# POWER.net
KiCad netlist of a schematic drawn in Altium Designer
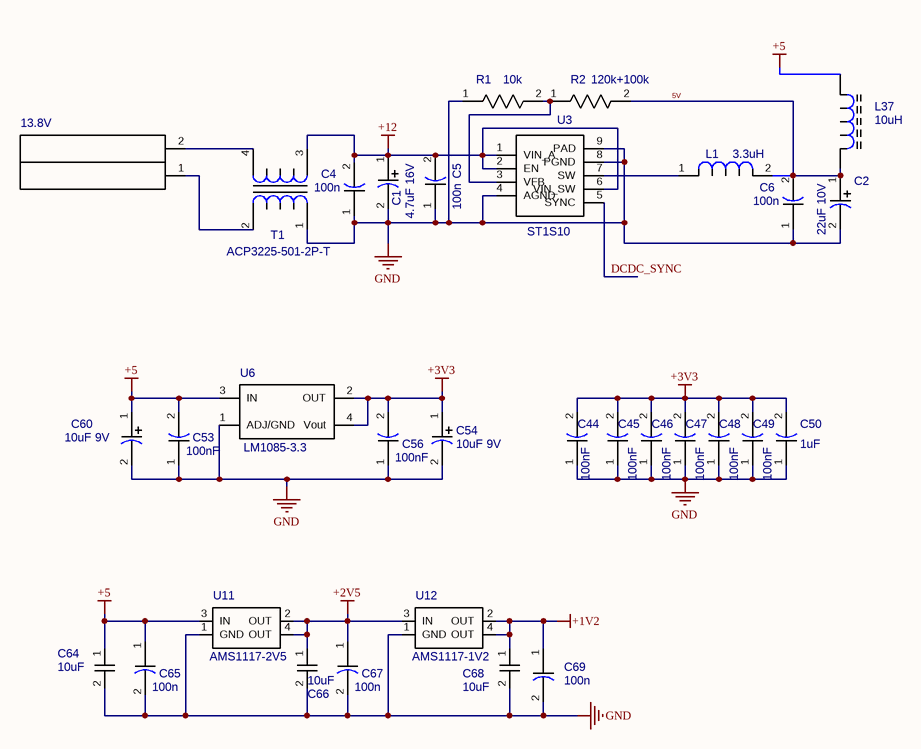
[diagram p0: POWER.SchDoc]

(export (version "E")
  (design (tool "Eeschema 10.0.6"))
  (components
    (comp (ref "13.8V") (value "JX2") (footprint "JX2") (libsource (lib "*") (part "JX2")))
    (comp (ref "C1")
      (value "4.7uF 16V")
      (footprint "CAPAE_6.6x6.6h5.4")
      (description "CAPAE_6.6x6.6h5.4")
      (libsource (lib "*") (part "CAPAE_6.6x6.6h5.4"))
    )
    (comp (ref "C2")
      (value "22uF 10V")
      (footprint "CAPAE_4.3x4.3h5.4")
      (description "CAPAE_4.3x4.3h5.4")
      (libsource (lib "*") (part "CAPAE_4.3x4.3h5.4"))
    )
    (comp (ref "C4")
      (value "100n")
      (footprint "CAP_0805")
      (description "CAP_0805")
      (libsource (lib "*") (part "CAP_0805"))
    )
    (comp (ref "C5")
      (value "100n")
      (footprint "CAP_0805")
      (description "CAP_0805")
      (libsource (lib "*") (part "CAP_0805"))
    )
    (comp (ref "C6")
      (value "100n")
      (footprint "CAP_0805")
      (description "CAP_0805")
      (libsource (lib "*") (part "CAP_0805"))
    )
    (comp (ref "C44")
      (value "100nF")
      (footprint "CAP_0805")
      (description "CAP_0805")
      (libsource (lib "*") (part "CAP_0805"))
    )
    (comp (ref "C45")
      (value "100nF")
      (footprint "CAP_0805")
      (description "CAP_0805")
      (libsource (lib "*") (part "CAP_0805"))
    )
    (comp (ref "C46")
      (value "100nF")
      (footprint "CAP_0805")
      (description "CAP_0805")
      (libsource (lib "*") (part "CAP_0805"))
    )
    (comp (ref "C47")
      (value "100nF")
      (footprint "CAP_0805")
      (description "CAP_0805")
      (libsource (lib "*") (part "CAP_0805"))
    )
    (comp (ref "C48")
      (value "100nF")
      (footprint "CAP_0805")
      (description "CAP_0805")
      (libsource (lib "*") (part "CAP_0805"))
    )
    (comp (ref "C49")
      (value "100nF")
      (footprint "CAP_0805")
      (description "CAP_0805")
      (libsource (lib "*") (part "CAP_0805"))
    )
    (comp (ref "C50")
      (value "1uF")
      (footprint "CAP_0805")
      (description "CAP_0805")
      (fields (field (name "Comment") "10uF"))
      (libsource (lib "*") (part "CAP_0805"))
    )
    (comp (ref "C53")
      (value "100nF")
      (footprint "CAP_0805")
      (description "CAP_0805")
      (libsource (lib "*") (part "CAP_0805"))
    )
    (comp (ref "C54")
      (value "10uF 9V")
      (footprint "CAPAE_4.3x4.3h5.4")
      (description "CAPAE_4.3x4.3h5.4")
      (libsource (lib "*") (part "CAPAE_4.3x4.3h5.4"))
    )
    (comp (ref "C56")
      (value "100nF")
      (footprint "CAP_0805")
      (description "CAP_0805")
      (libsource (lib "*") (part "CAP_0805"))
    )
    (comp (ref "C60")
      (value "10uF 9V")
      (footprint "CAPAE_4.3x4.3h5.4")
      (description "CAPAE_4.3x4.3h5.4")
      (libsource (lib "*") (part "CAPAE_4.3x4.3h5.4"))
    )
    (comp (ref "C64")
      (value "10uF")
      (footprint "C0805")
      (description "C0805")
      (libsource (lib "*") (part "C0805"))
    )
    (comp (ref "C65")
      (value "100n")
      (footprint "CAP_0805")
      (description "CAP_0805")
      (libsource (lib "*") (part "CAP_0805"))
    )
    (comp (ref "C66")
      (value "10uF")
      (footprint "C0805")
      (description "C0805")
      (libsource (lib "*") (part "C0805"))
    )
    (comp (ref "C67")
      (value "100n")
      (footprint "CAP_0805")
      (description "CAP_0805")
      (libsource (lib "*") (part "CAP_0805"))
    )
    (comp (ref "C68")
      (value "10uF")
      (footprint "C0805")
      (description "C0805")
      (libsource (lib "*") (part "C0805"))
    )
    (comp (ref "C69")
      (value "100n")
      (footprint "CAP_0805")
      (description "CAP_0805")
      (libsource (lib "*") (part "CAP_0805"))
    )
    (comp (ref "L1")
      (value "3.3uH")
      (footprint "IND_1812")
      (description "IND_1812")
      (libsource (lib "*") (part "IND_1812"))
    )
    (comp (ref "L37")
      (value "10uH")
      (footprint "IND_FERRITE_CORE")
      (description "Inductor")
      (libsource (lib "MOTHERBOARD_1") (part "IND_FERRITE_CORE"))
    )
    (comp (ref "R1")
      (value "10k")
      (footprint "RES_0805")
      (description "RES_0805")
      (libsource (lib "*") (part "RES_0805"))
    )
    (comp (ref "R2")
      (value "120k+100k")
      (footprint "RES_0805")
      (description "RES_0805")
      (libsource (lib "*") (part "RES_0805"))
    )
    (comp (ref "T1")
      (value "ACP3225-501-2P-T")
      (footprint "TRANSF_ICORE")
      (description "Transformer")
      (libsource (lib "*") (part "TRANSF_ICORE"))
    )
    (comp (ref "U3") (value "ST1S10") (footprint "ST1S10") (libsource (lib "*") (part "ST1S10")))
    (comp (ref "U6") (value "LM1085-3.3") (footprint "LM1085-3.3") (libsource (lib "*") (part "LM1085-3.3")))
    (comp (ref "U11") (value "AMS1117-2V5") (footprint "AMS1117") (libsource (lib "*") (part "AMS1117")))
    (comp (ref "U12") (value "AMS1117-1V2") (footprint "AMS1117") (libsource (lib "*") (part "AMS1117")))
  )
  (nets
    (net (code "1") (name "+1V2") (class "Default")
      (node (ref "C68") (pin "1") (pinfunction "1_1") (pintype "passive"))
      (node (ref "C69") (pin "1") (pinfunction "1_1") (pintype "passive"))
      (node (ref "U12") (pin "2") (pinfunction "OUT_2") (pintype "passive"))
      (node (ref "U12") (pin "4") (pinfunction "OUT_4") (pintype "passive"))
    )
    (net (code "2") (name "+2V5") (class "Default")
      (node (ref "C66") (pin "1") (pinfunction "1_1") (pintype "passive"))
      (node (ref "C67") (pin "1") (pinfunction "1_1") (pintype "passive"))
      (node (ref "U11") (pin "2") (pinfunction "OUT_2") (pintype "passive"))
      (node (ref "U11") (pin "4") (pinfunction "OUT_4") (pintype "passive"))
      (node (ref "U12") (pin "3") (pinfunction "IN_3") (pintype "passive"))
    )
    (net (code "3") (name "+3V3") (class "Default")
      (node (ref "C44") (pin "2") (pinfunction "2_2") (pintype "passive"))
      (node (ref "C45") (pin "2") (pinfunction "2_2") (pintype "passive"))
      (node (ref "C46") (pin "2") (pinfunction "2_2") (pintype "passive"))
      (node (ref "C47") (pin "2") (pinfunction "2_2") (pintype "passive"))
      (node (ref "C48") (pin "2") (pinfunction "2_2") (pintype "passive"))
      (node (ref "C49") (pin "2") (pinfunction "2_2") (pintype "passive"))
      (node (ref "C50") (pin "2") (pinfunction "2_2") (pintype "passive"))
      (node (ref "C54") (pin "1") (pinfunction "PLUS_1") (pintype "passive"))
      (node (ref "C56") (pin "2") (pinfunction "2_2") (pintype "passive"))
      (node (ref "U6") (pin "2") (pinfunction "OUT_2") (pintype "passive"))
      (node (ref "U6") (pin "4") (pinfunction "Vout_4") (pintype "passive"))
    )
    (net (code "4") (name "+5") (class "Default")
      (node (ref "C53") (pin "2") (pinfunction "2_2") (pintype "passive"))
      (node (ref "C60") (pin "1") (pinfunction "PLUS_1") (pintype "passive"))
      (node (ref "C64") (pin "1") (pinfunction "1_1") (pintype "passive"))
      (node (ref "C65") (pin "1") (pinfunction "1_1") (pintype "passive"))
      (node (ref "L37") (pin "1") (pinfunction "A_1") (pintype "passive"))
      (node (ref "U11") (pin "3") (pinfunction "IN_3") (pintype "passive"))
      (node (ref "U6") (pin "3") (pinfunction "IN_3") (pintype "passive"))
    )
    (net (code "5") (name "+12") (class "Default")
      (node (ref "C1") (pin "1") (pinfunction "PLUS_1") (pintype "passive"))
      (node (ref "C4") (pin "2") (pinfunction "2_2") (pintype "passive"))
      (node (ref "C5") (pin "2") (pinfunction "2_2") (pintype "passive"))
      (node (ref "T1") (pin "3") (pinfunction "P1_3") (pintype "passive"))
      (node (ref "U3") (pin "1") (pinfunction "VIN_A_1") (pintype "passive"))
      (node (ref "U3") (pin "2") (pinfunction "EN_2") (pintype "passive"))
      (node (ref "U3") (pin "6") (pinfunction "VIN_SW_6") (pintype "passive"))
    )
    (net (code "6") (name "/5V") (class "Default")
      (node (ref "C2") (pin "1") (pinfunction "PLUS_1") (pintype "passive"))
      (node (ref "C6") (pin "2") (pinfunction "2_2") (pintype "passive"))
      (node (ref "L1") (pin "2") (pinfunction "2_2") (pintype "passive"))
      (node (ref "L37") (pin "2") (pinfunction "B_2") (pintype "passive"))
      (node (ref "R2") (pin "2") (pinfunction "2_2") (pintype "passive"))
    )
    (net (code "7") (name "/DCDC_SYNC") (class "Default")
      (node (ref "U3") (pin "5") (pinfunction "SYNC_5") (pintype "passive"))
    )
    (net (code "8") (name "GND") (class "Default")
      (node (ref "C1") (pin "2") (pinfunction "MINUS_2") (pintype "passive"))
      (node (ref "C2") (pin "2") (pinfunction "MINUS_2") (pintype "passive"))
      (node (ref "C4") (pin "1") (pinfunction "1_1") (pintype "passive"))
      (node (ref "C44") (pin "1") (pinfunction "1_1") (pintype "passive"))
      (node (ref "C45") (pin "1") (pinfunction "1_1") (pintype "passive"))
      (node (ref "C46") (pin "1") (pinfunction "1_1") (pintype "passive"))
      (node (ref "C47") (pin "1") (pinfunction "1_1") (pintype "passive"))
      (node (ref "C48") (pin "1") (pinfunction "1_1") (pintype "passive"))
      (node (ref "C49") (pin "1") (pinfunction "1_1") (pintype "passive"))
      (node (ref "C5") (pin "1") (pinfunction "1_1") (pintype "passive"))
      (node (ref "C50") (pin "1") (pinfunction "1_1") (pintype "passive"))
      (node (ref "C53") (pin "1") (pinfunction "1_1") (pintype "passive"))
      (node (ref "C54") (pin "2") (pinfunction "MINUS_2") (pintype "passive"))
      (node (ref "C56") (pin "1") (pinfunction "1_1") (pintype "passive"))
      (node (ref "C6") (pin "1") (pinfunction "1_1") (pintype "passive"))
      (node (ref "C60") (pin "2") (pinfunction "MINUS_2") (pintype "passive"))
      (node (ref "C64") (pin "2") (pinfunction "2_2") (pintype "passive"))
      (node (ref "C65") (pin "2") (pinfunction "2_2") (pintype "passive"))
      (node (ref "C66") (pin "2") (pinfunction "2_2") (pintype "passive"))
      (node (ref "C67") (pin "2") (pinfunction "2_2") (pintype "passive"))
      (node (ref "C68") (pin "2") (pinfunction "2_2") (pintype "passive"))
      (node (ref "C69") (pin "2") (pinfunction "2_2") (pintype "passive"))
      (node (ref "R1") (pin "1") (pinfunction "1_1") (pintype "passive"))
      (node (ref "T1") (pin "1") (pinfunction "S1_1") (pintype "passive"))
      (node (ref "U11") (pin "1") (pinfunction "GND_1") (pintype "passive"))
      (node (ref "U12") (pin "1") (pinfunction "GND_1") (pintype "passive"))
      (node (ref "U3") (pin "4") (pinfunction "AGND_4") (pintype "passive"))
      (node (ref "U3") (pin "8") (pinfunction "PGND_8") (pintype "passive"))
      (node (ref "U3") (pin "9") (pinfunction "PAD_9") (pintype "passive"))
      (node (ref "U6") (pin "1") (pinfunction "ADJ/GND_1") (pintype "passive"))
    )
    (net (code "9") (name "Net-(13.8V-1)") (class "Default")
      (node (ref "13.8V") (pin "2") (pinfunction "1_2") (pintype "passive"))
      (node (ref "T1") (pin "4") (pinfunction "P2_4") (pintype "passive"))
    )
    (net (code "10") (name "Net-(13.8V-2)") (class "Default")
      (node (ref "13.8V") (pin "1") (pinfunction "2_1") (pintype "passive"))
      (node (ref "T1") (pin "2") (pinfunction "S2_2") (pintype "passive"))
    )
    (net (code "11") (name "Net-(U3-SW)") (class "Default")
      (node (ref "L1") (pin "1") (pinfunction "1_1") (pintype "passive"))
      (node (ref "U3") (pin "7") (pinfunction "SW_7") (pintype "passive"))
    )
    (net (code "12") (name "Net-(U3-VFB)") (class "Default")
      (node (ref "R1") (pin "2") (pinfunction "2_2") (pintype "passive"))
      (node (ref "R2") (pin "1") (pinfunction "1_1") (pintype "passive"))
      (node (ref "U3") (pin "3") (pinfunction "VFB_3") (pintype "passive"))
    )
  )
)
